# STM32_DEV_Board_Connectors.net
KiCad netlist of a schematic drawn in Altium Designer
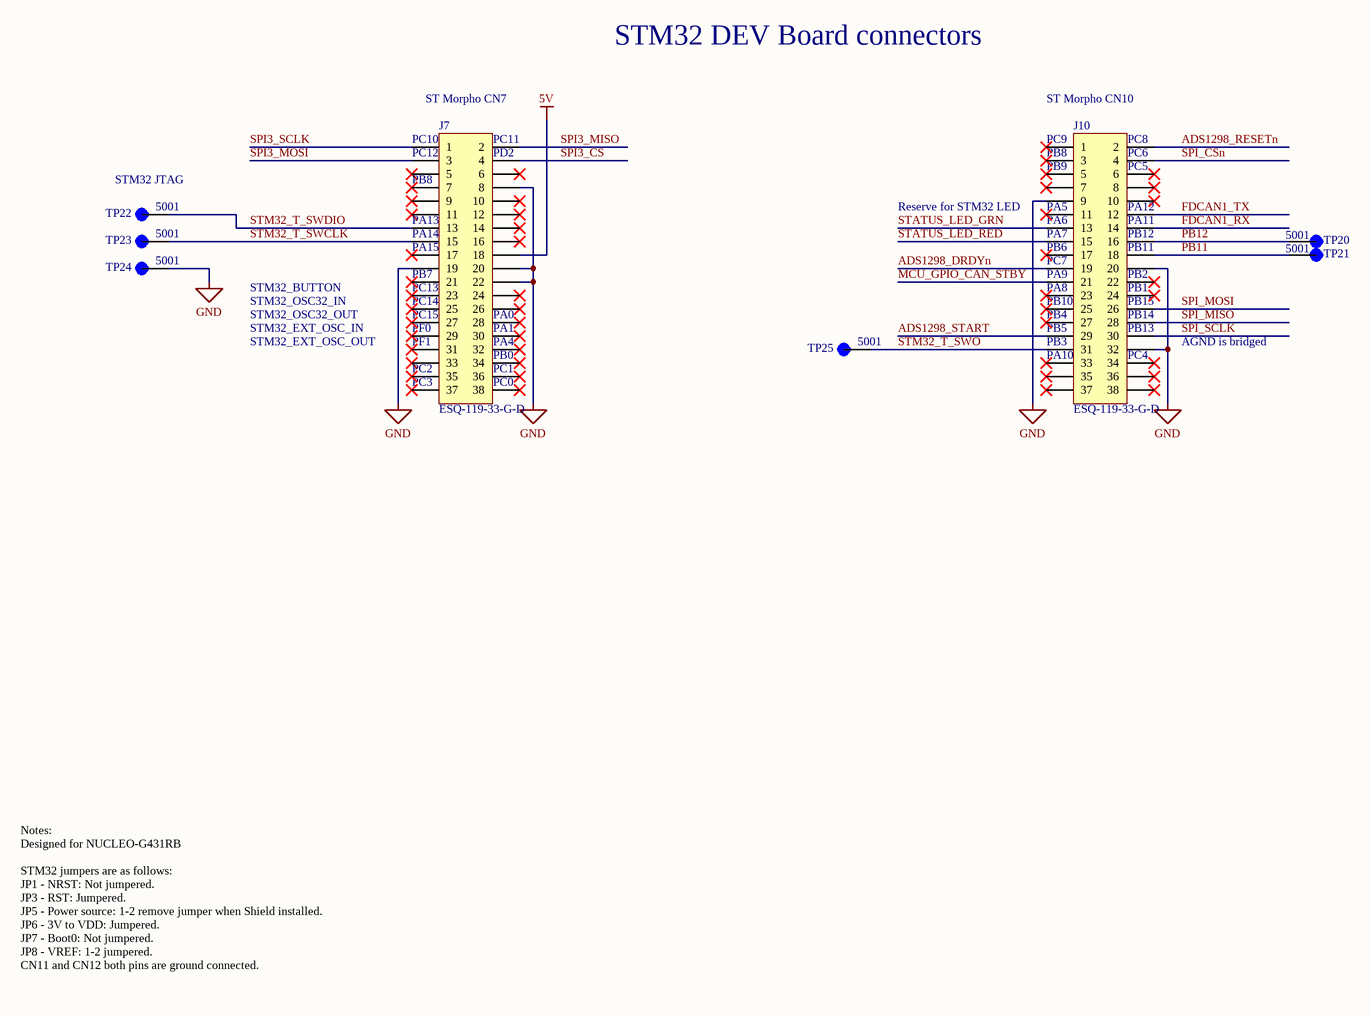
[diagram p0: STM32_DEV_Board_Connectors.SchDoc]

(export (version "E")
  (design (tool "Eeschema 10.0.6"))
  (components
    (comp (ref "J7")
      (value "ESQ-119-33-G-D")
      (footprint "J_SAMTEC_ESQ-119-33-G-D")
      (description "CONN SOCKET 38POS 0.1 GOLD PCB ELEVETED TH")
      (fields (field (name "MFG") "Samtec"))
      (libsource (lib "Myomo_SCH_Library") (part "J_SAMTEC_ESQ-119-33-G-D"))
    )
    (comp (ref "J10")
      (value "ESQ-119-33-G-D")
      (footprint "J_SAMTEC_ESQ-119-33-G-D")
      (description "CONN SOCKET 38POS 0.1 GOLD PCB ELEVETED TH")
      (fields (field (name "MFG") "Samtec"))
      (libsource (lib "Myomo_SCH_Library") (part "J_SAMTEC_ESQ-119-33-G-D"))
    )
    (comp (ref "TP20")
      (value "5001")
      (footprint "TP_CLIP_BLK_5001")
      (description "PC TEST POINT MINIATURE BLACK")
      (fields (field (name "MFG") "Keystone Electronics"))
      (libsource (lib "Myomo_SCH_Library") (part "TP_CLIP_BLK_5001"))
    )
    (comp (ref "TP21")
      (value "5001")
      (footprint "TP_CLIP_BLK_5001")
      (description "PC TEST POINT MINIATURE BLACK")
      (fields (field (name "MFG") "Keystone Electronics"))
      (libsource (lib "Myomo_SCH_Library") (part "TP_CLIP_BLK_5001"))
    )
    (comp (ref "TP22")
      (value "5001")
      (footprint "TP_CLIP_BLK_5001")
      (description "PC TEST POINT MINIATURE BLACK")
      (fields (field (name "MFG") "Keystone Electronics"))
      (libsource (lib "Myomo_SCH_Library") (part "TP_CLIP_BLK_5001"))
    )
    (comp (ref "TP23")
      (value "5001")
      (footprint "TP_CLIP_BLK_5001")
      (description "PC TEST POINT MINIATURE BLACK")
      (fields (field (name "MFG") "Keystone Electronics"))
      (libsource (lib "Myomo_SCH_Library") (part "TP_CLIP_BLK_5001"))
    )
    (comp (ref "TP24")
      (value "5001")
      (footprint "TP_CLIP_BLK_5001")
      (description "PC TEST POINT MINIATURE BLACK")
      (fields (field (name "MFG") "Keystone Electronics"))
      (libsource (lib "Myomo_SCH_Library") (part "TP_CLIP_BLK_5001"))
    )
    (comp (ref "TP25")
      (value "5001")
      (footprint "TP_CLIP_BLK_5001")
      (description "PC TEST POINT MINIATURE BLACK")
      (fields (field (name "MFG") "Keystone Electronics"))
      (libsource (lib "Myomo_SCH_Library") (part "TP_CLIP_BLK_5001"))
    )
  )
  (nets
    (net (code "1") (name "/ADS1298_DRDYn") (class "Default")
      (node (ref "J10") (pin "19") (pinfunction "19_19") (pintype "passive"))
    )
    (net (code "2") (name "/ADS1298_RESETn") (class "Default")
      (node (ref "J10") (pin "2") (pinfunction "2_2") (pintype "passive"))
    )
    (net (code "3") (name "/ADS1298_START") (class "Default")
      (node (ref "J10") (pin "29") (pinfunction "29_29") (pintype "passive"))
    )
    (net (code "4") (name "/FDCAN1_RX") (class "Default")
      (node (ref "J10") (pin "14") (pinfunction "14_14") (pintype "passive"))
    )
    (net (code "5") (name "/FDCAN1_TX") (class "Default")
      (node (ref "J10") (pin "12") (pinfunction "12_12") (pintype "passive"))
    )
    (net (code "6") (name "/MCU_GPIO_CAN_STBY") (class "Default")
      (node (ref "J10") (pin "21") (pinfunction "21_21") (pintype "passive"))
    )
    (net (code "7") (name "/PB11") (class "Default")
      (node (ref "J10") (pin "18") (pinfunction "18_18") (pintype "passive"))
      (node (ref "TP21") (pin "TP") (pinfunction "TP_TP") (pintype "passive"))
    )
    (net (code "8") (name "/PB12") (class "Default")
      (node (ref "J10") (pin "16") (pinfunction "16_16") (pintype "passive"))
      (node (ref "TP20") (pin "TP") (pinfunction "TP_TP") (pintype "passive"))
    )
    (net (code "9") (name "/SPI3_CS") (class "Default")
      (node (ref "J7") (pin "4") (pinfunction "4_4") (pintype "passive"))
    )
    (net (code "10") (name "/SPI3_MISO") (class "Default")
      (node (ref "J7") (pin "2") (pinfunction "2_2") (pintype "passive"))
    )
    (net (code "11") (name "/SPI3_MOSI") (class "Default")
      (node (ref "J7") (pin "3") (pinfunction "3_3") (pintype "passive"))
    )
    (net (code "12") (name "/SPI3_SCLK") (class "Default")
      (node (ref "J7") (pin "1") (pinfunction "1_1") (pintype "passive"))
    )
    (net (code "13") (name "/SPI_CSn") (class "Default")
      (node (ref "J10") (pin "4") (pinfunction "4_4") (pintype "passive"))
    )
    (net (code "14") (name "/SPI_MISO") (class "Default")
      (node (ref "J10") (pin "28") (pinfunction "28_28") (pintype "passive"))
    )
    (net (code "15") (name "/SPI_MOSI") (class "Default")
      (node (ref "J10") (pin "26") (pinfunction "26_26") (pintype "passive"))
    )
    (net (code "16") (name "/SPI_SCLK") (class "Default")
      (node (ref "J10") (pin "30") (pinfunction "30_30") (pintype "passive"))
    )
    (net (code "17") (name "/STATUS_LED_GRN") (class "Default")
      (node (ref "J10") (pin "13") (pinfunction "13_13") (pintype "passive"))
    )
    (net (code "18") (name "/STATUS_LED_RED") (class "Default")
      (node (ref "J10") (pin "15") (pinfunction "15_15") (pintype "passive"))
    )
    (net (code "19") (name "/STM32_T_SWCLK") (class "Default")
      (node (ref "J7") (pin "15") (pinfunction "15_15") (pintype "passive"))
      (node (ref "TP23") (pin "TP") (pinfunction "TP_TP") (pintype "passive"))
    )
    (net (code "20") (name "/STM32_T_SWDIO") (class "Default")
      (node (ref "J7") (pin "13") (pinfunction "13_13") (pintype "passive"))
      (node (ref "TP22") (pin "TP") (pinfunction "TP_TP") (pintype "passive"))
    )
    (net (code "21") (name "/STM32_T_SWO") (class "Default")
      (node (ref "J10") (pin "31") (pinfunction "31_31") (pintype "passive"))
      (node (ref "TP25") (pin "TP") (pinfunction "TP_TP") (pintype "passive"))
    )
    (net (code "22") (name "5V") (class "Default")
      (node (ref "J7") (pin "18") (pinfunction "18_18") (pintype "passive"))
    )
    (net (code "23") (name "GND") (class "Default")
      (node (ref "J10") (pin "20") (pinfunction "20_20") (pintype "passive"))
      (node (ref "J10") (pin "32") (pinfunction "32_32") (pintype "passive"))
      (node (ref "J10") (pin "9") (pinfunction "9_9") (pintype "passive"))
      (node (ref "J7") (pin "19") (pinfunction "19_19") (pintype "passive"))
      (node (ref "J7") (pin "20") (pinfunction "20_20") (pintype "passive"))
      (node (ref "J7") (pin "22") (pinfunction "22_22") (pintype "passive"))
      (node (ref "J7") (pin "8") (pinfunction "8_8") (pintype "passive"))
      (node (ref "TP24") (pin "TP") (pinfunction "TP_TP") (pintype "passive"))
    )
    (net (code "24") (name "unconnected-(J7-Pad5)") (class "Default")
      (node (ref "J7") (pin "5") (pinfunction "5_5") (pintype "passive+no_connect"))
    )
    (net (code "25") (name "unconnected-(J7-Pad6)") (class "Default")
      (node (ref "J7") (pin "6") (pinfunction "6_6") (pintype "passive+no_connect"))
    )
    (net (code "26") (name "unconnected-(J7-Pad7)") (class "Default")
      (node (ref "J7") (pin "7") (pinfunction "7_7") (pintype "passive+no_connect"))
    )
    (net (code "27") (name "unconnected-(J7-Pad9)") (class "Default")
      (node (ref "J7") (pin "9") (pinfunction "9_9") (pintype "passive+no_connect"))
    )
    (net (code "28") (name "unconnected-(J7-Pad10)") (class "Default")
      (node (ref "J7") (pin "10") (pinfunction "10_10") (pintype "passive+no_connect"))
    )
    (net (code "29") (name "unconnected-(J7-Pad11)") (class "Default")
      (node (ref "J7") (pin "11") (pinfunction "11_11") (pintype "passive+no_connect"))
    )
    (net (code "30") (name "unconnected-(J7-Pad12)") (class "Default")
      (node (ref "J7") (pin "12") (pinfunction "12_12") (pintype "passive+no_connect"))
    )
    (net (code "31") (name "unconnected-(J7-Pad14)") (class "Default")
      (node (ref "J7") (pin "14") (pinfunction "14_14") (pintype "passive+no_connect"))
    )
    (net (code "32") (name "unconnected-(J7-Pad16)") (class "Default")
      (node (ref "J7") (pin "16") (pinfunction "16_16") (pintype "passive+no_connect"))
    )
    (net (code "33") (name "unconnected-(J7-Pad17)") (class "Default")
      (node (ref "J7") (pin "17") (pinfunction "17_17") (pintype "passive+no_connect"))
    )
    (net (code "34") (name "unconnected-(J7-Pad21)") (class "Default")
      (node (ref "J7") (pin "21") (pinfunction "21_21") (pintype "passive+no_connect"))
    )
    (net (code "35") (name "unconnected-(J7-Pad23)") (class "Default")
      (node (ref "J7") (pin "23") (pinfunction "23_23") (pintype "passive+no_connect"))
    )
    (net (code "36") (name "unconnected-(J7-Pad24)") (class "Default")
      (node (ref "J7") (pin "24") (pinfunction "24_24") (pintype "passive+no_connect"))
    )
    (net (code "37") (name "unconnected-(J7-Pad25)") (class "Default")
      (node (ref "J7") (pin "25") (pinfunction "25_25") (pintype "passive+no_connect"))
    )
    (net (code "38") (name "unconnected-(J7-Pad26)") (class "Default")
      (node (ref "J7") (pin "26") (pinfunction "26_26") (pintype "passive+no_connect"))
    )
    (net (code "39") (name "unconnected-(J7-Pad27)") (class "Default")
      (node (ref "J7") (pin "27") (pinfunction "27_27") (pintype "passive+no_connect"))
    )
    (net (code "40") (name "unconnected-(J7-Pad28)") (class "Default")
      (node (ref "J7") (pin "28") (pinfunction "28_28") (pintype "passive+no_connect"))
    )
    (net (code "41") (name "unconnected-(J7-Pad29)") (class "Default")
      (node (ref "J7") (pin "29") (pinfunction "29_29") (pintype "passive+no_connect"))
    )
    (net (code "42") (name "unconnected-(J7-Pad30)") (class "Default")
      (node (ref "J7") (pin "30") (pinfunction "30_30") (pintype "passive+no_connect"))
    )
    (net (code "43") (name "unconnected-(J7-Pad31)") (class "Default")
      (node (ref "J7") (pin "31") (pinfunction "31_31") (pintype "passive+no_connect"))
    )
    (net (code "44") (name "unconnected-(J7-Pad32)") (class "Default")
      (node (ref "J7") (pin "32") (pinfunction "32_32") (pintype "passive+no_connect"))
    )
    (net (code "45") (name "unconnected-(J7-Pad33)") (class "Default")
      (node (ref "J7") (pin "33") (pinfunction "33_33") (pintype "passive+no_connect"))
    )
    (net (code "46") (name "unconnected-(J7-Pad34)") (class "Default")
      (node (ref "J7") (pin "34") (pinfunction "34_34") (pintype "passive+no_connect"))
    )
    (net (code "47") (name "unconnected-(J7-Pad35)") (class "Default")
      (node (ref "J7") (pin "35") (pinfunction "35_35") (pintype "passive+no_connect"))
    )
    (net (code "48") (name "unconnected-(J7-Pad36)") (class "Default")
      (node (ref "J7") (pin "36") (pinfunction "36_36") (pintype "passive+no_connect"))
    )
    (net (code "49") (name "unconnected-(J7-Pad37)") (class "Default")
      (node (ref "J7") (pin "37") (pinfunction "37_37") (pintype "passive+no_connect"))
    )
    (net (code "50") (name "unconnected-(J7-Pad38)") (class "Default")
      (node (ref "J7") (pin "38") (pinfunction "38_38") (pintype "passive+no_connect"))
    )
    (net (code "51") (name "unconnected-(J10-Pad1)") (class "Default")
      (node (ref "J10") (pin "1") (pinfunction "1_1") (pintype "passive+no_connect"))
    )
    (net (code "52") (name "unconnected-(J10-Pad3)") (class "Default")
      (node (ref "J10") (pin "3") (pinfunction "3_3") (pintype "passive+no_connect"))
    )
    (net (code "53") (name "unconnected-(J10-Pad5)") (class "Default")
      (node (ref "J10") (pin "5") (pinfunction "5_5") (pintype "passive+no_connect"))
    )
    (net (code "54") (name "unconnected-(J10-Pad6)") (class "Default")
      (node (ref "J10") (pin "6") (pinfunction "6_6") (pintype "passive+no_connect"))
    )
    (net (code "55") (name "unconnected-(J10-Pad7)") (class "Default")
      (node (ref "J10") (pin "7") (pinfunction "7_7") (pintype "passive+no_connect"))
    )
    (net (code "56") (name "unconnected-(J10-Pad8)") (class "Default")
      (node (ref "J10") (pin "8") (pinfunction "8_8") (pintype "passive+no_connect"))
    )
    (net (code "57") (name "unconnected-(J10-Pad10)") (class "Default")
      (node (ref "J10") (pin "10") (pinfunction "10_10") (pintype "passive+no_connect"))
    )
    (net (code "58") (name "unconnected-(J10-Pad11)") (class "Default")
      (node (ref "J10") (pin "11") (pinfunction "11_11") (pintype "passive+no_connect"))
    )
    (net (code "59") (name "unconnected-(J10-Pad17)") (class "Default")
      (node (ref "J10") (pin "17") (pinfunction "17_17") (pintype "passive+no_connect"))
    )
    (net (code "60") (name "unconnected-(J10-Pad22)") (class "Default")
      (node (ref "J10") (pin "22") (pinfunction "22_22") (pintype "passive+no_connect"))
    )
    (net (code "61") (name "unconnected-(J10-Pad23)") (class "Default")
      (node (ref "J10") (pin "23") (pinfunction "23_23") (pintype "passive+no_connect"))
    )
    (net (code "62") (name "unconnected-(J10-Pad24)") (class "Default")
      (node (ref "J10") (pin "24") (pinfunction "24_24") (pintype "passive+no_connect"))
    )
    (net (code "63") (name "unconnected-(J10-Pad25)") (class "Default")
      (node (ref "J10") (pin "25") (pinfunction "25_25") (pintype "passive+no_connect"))
    )
    (net (code "64") (name "unconnected-(J10-Pad27)") (class "Default")
      (node (ref "J10") (pin "27") (pinfunction "27_27") (pintype "passive+no_connect"))
    )
    (net (code "65") (name "unconnected-(J10-Pad33)") (class "Default")
      (node (ref "J10") (pin "33") (pinfunction "33_33") (pintype "passive+no_connect"))
    )
    (net (code "66") (name "unconnected-(J10-Pad34)") (class "Default")
      (node (ref "J10") (pin "34") (pinfunction "34_34") (pintype "passive+no_connect"))
    )
    (net (code "67") (name "unconnected-(J10-Pad35)") (class "Default")
      (node (ref "J10") (pin "35") (pinfunction "35_35") (pintype "passive+no_connect"))
    )
    (net (code "68") (name "unconnected-(J10-Pad36)") (class "Default")
      (node (ref "J10") (pin "36") (pinfunction "36_36") (pintype "passive+no_connect"))
    )
    (net (code "69") (name "unconnected-(J10-Pad37)") (class "Default")
      (node (ref "J10") (pin "37") (pinfunction "37_37") (pintype "passive+no_connect"))
    )
    (net (code "70") (name "unconnected-(J10-Pad38)") (class "Default")
      (node (ref "J10") (pin "38") (pinfunction "38_38") (pintype "passive+no_connect"))
    )
  )
)
